# InkTime.net
KiCad netlist of a schematic drawn in EAGLE
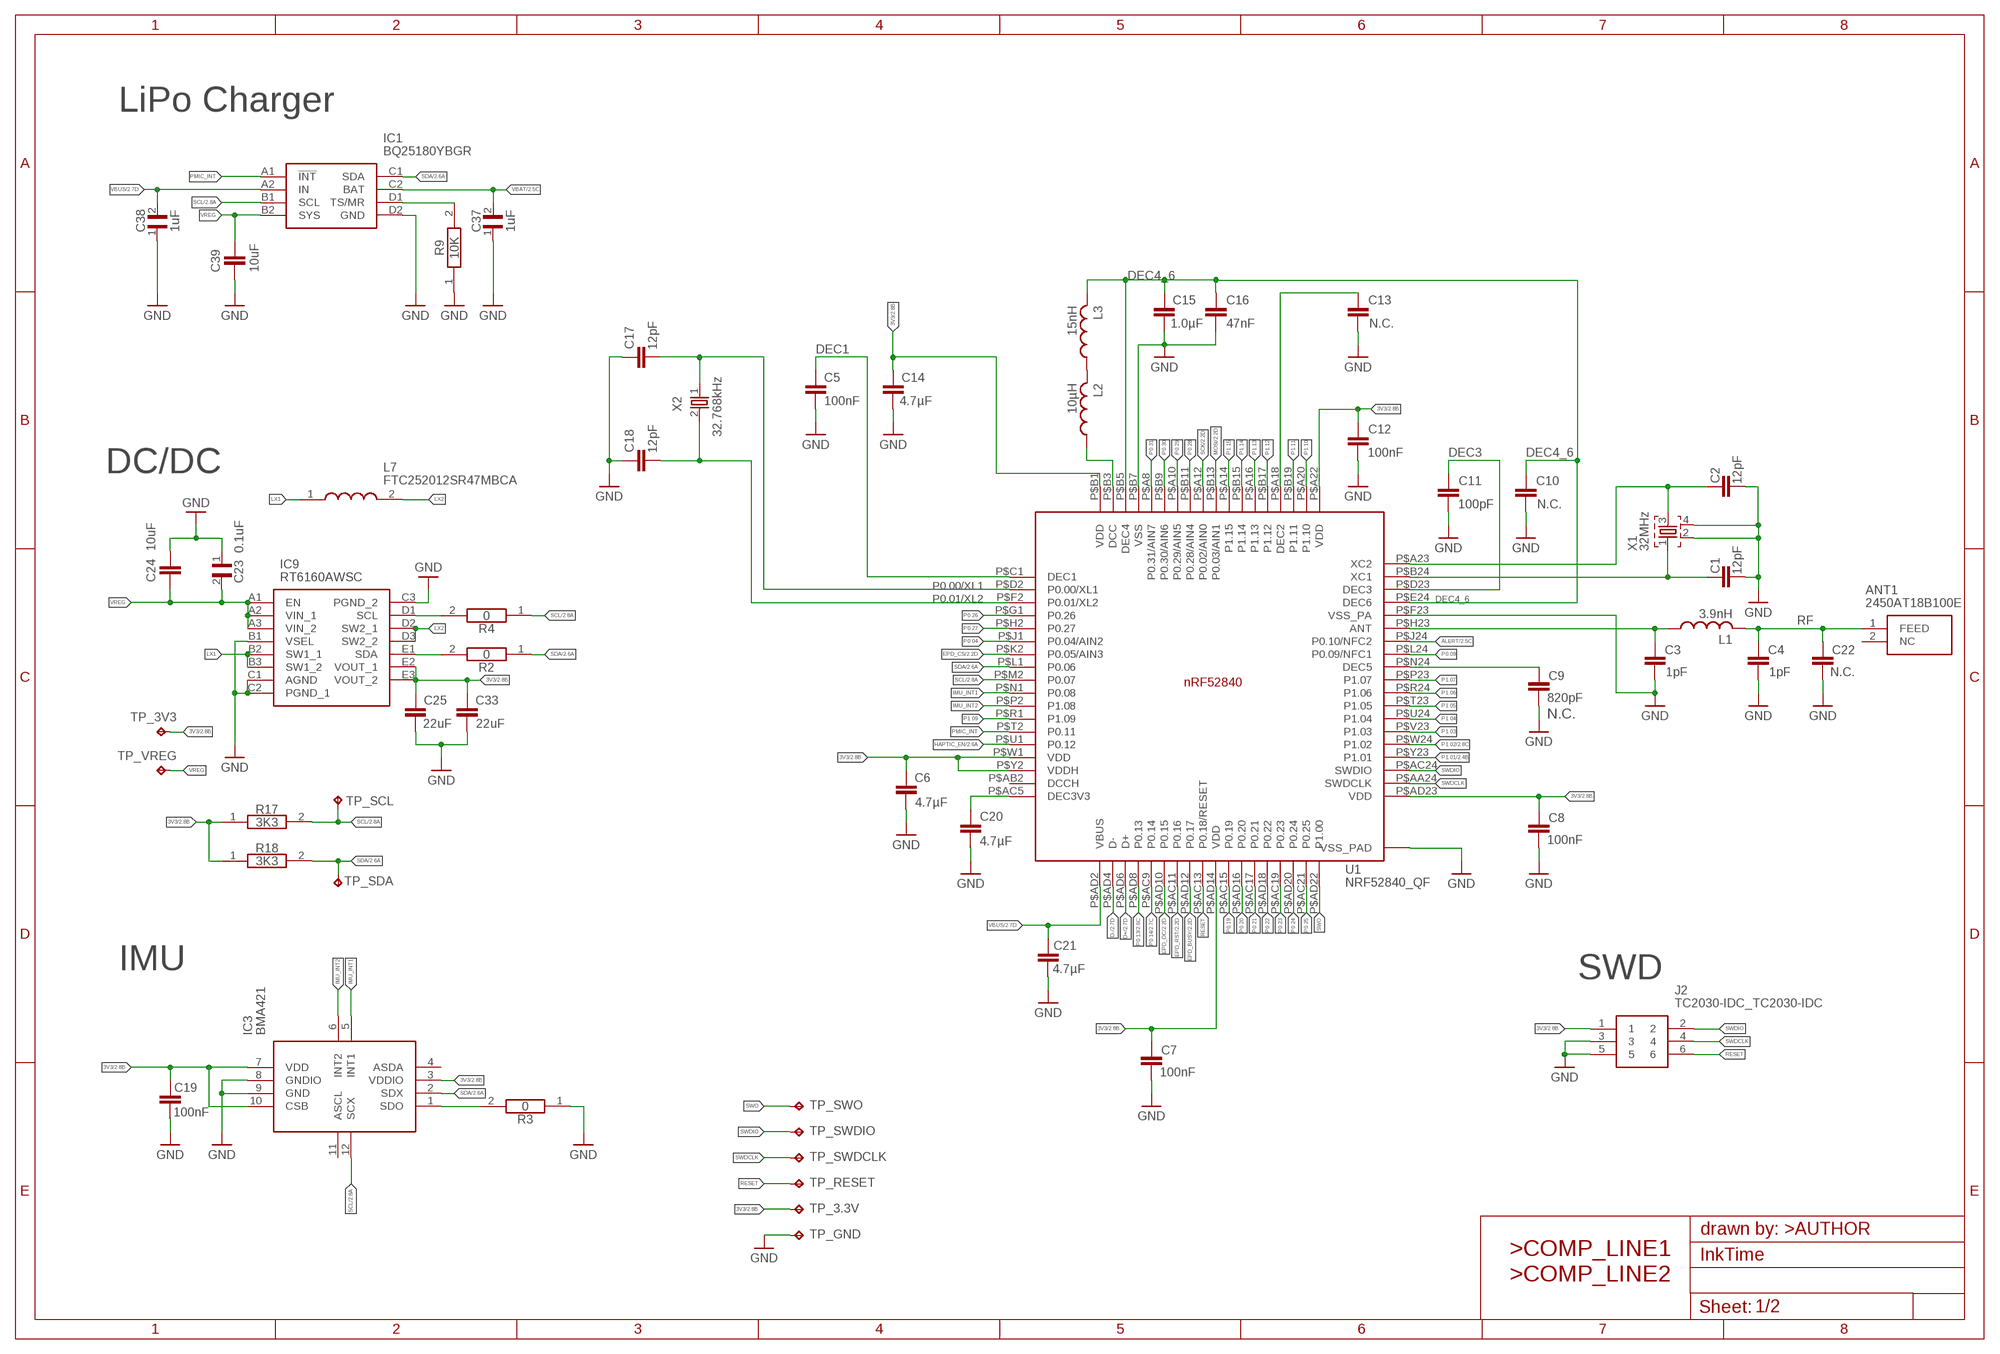
[diagram p0: schematic, sheet 1]
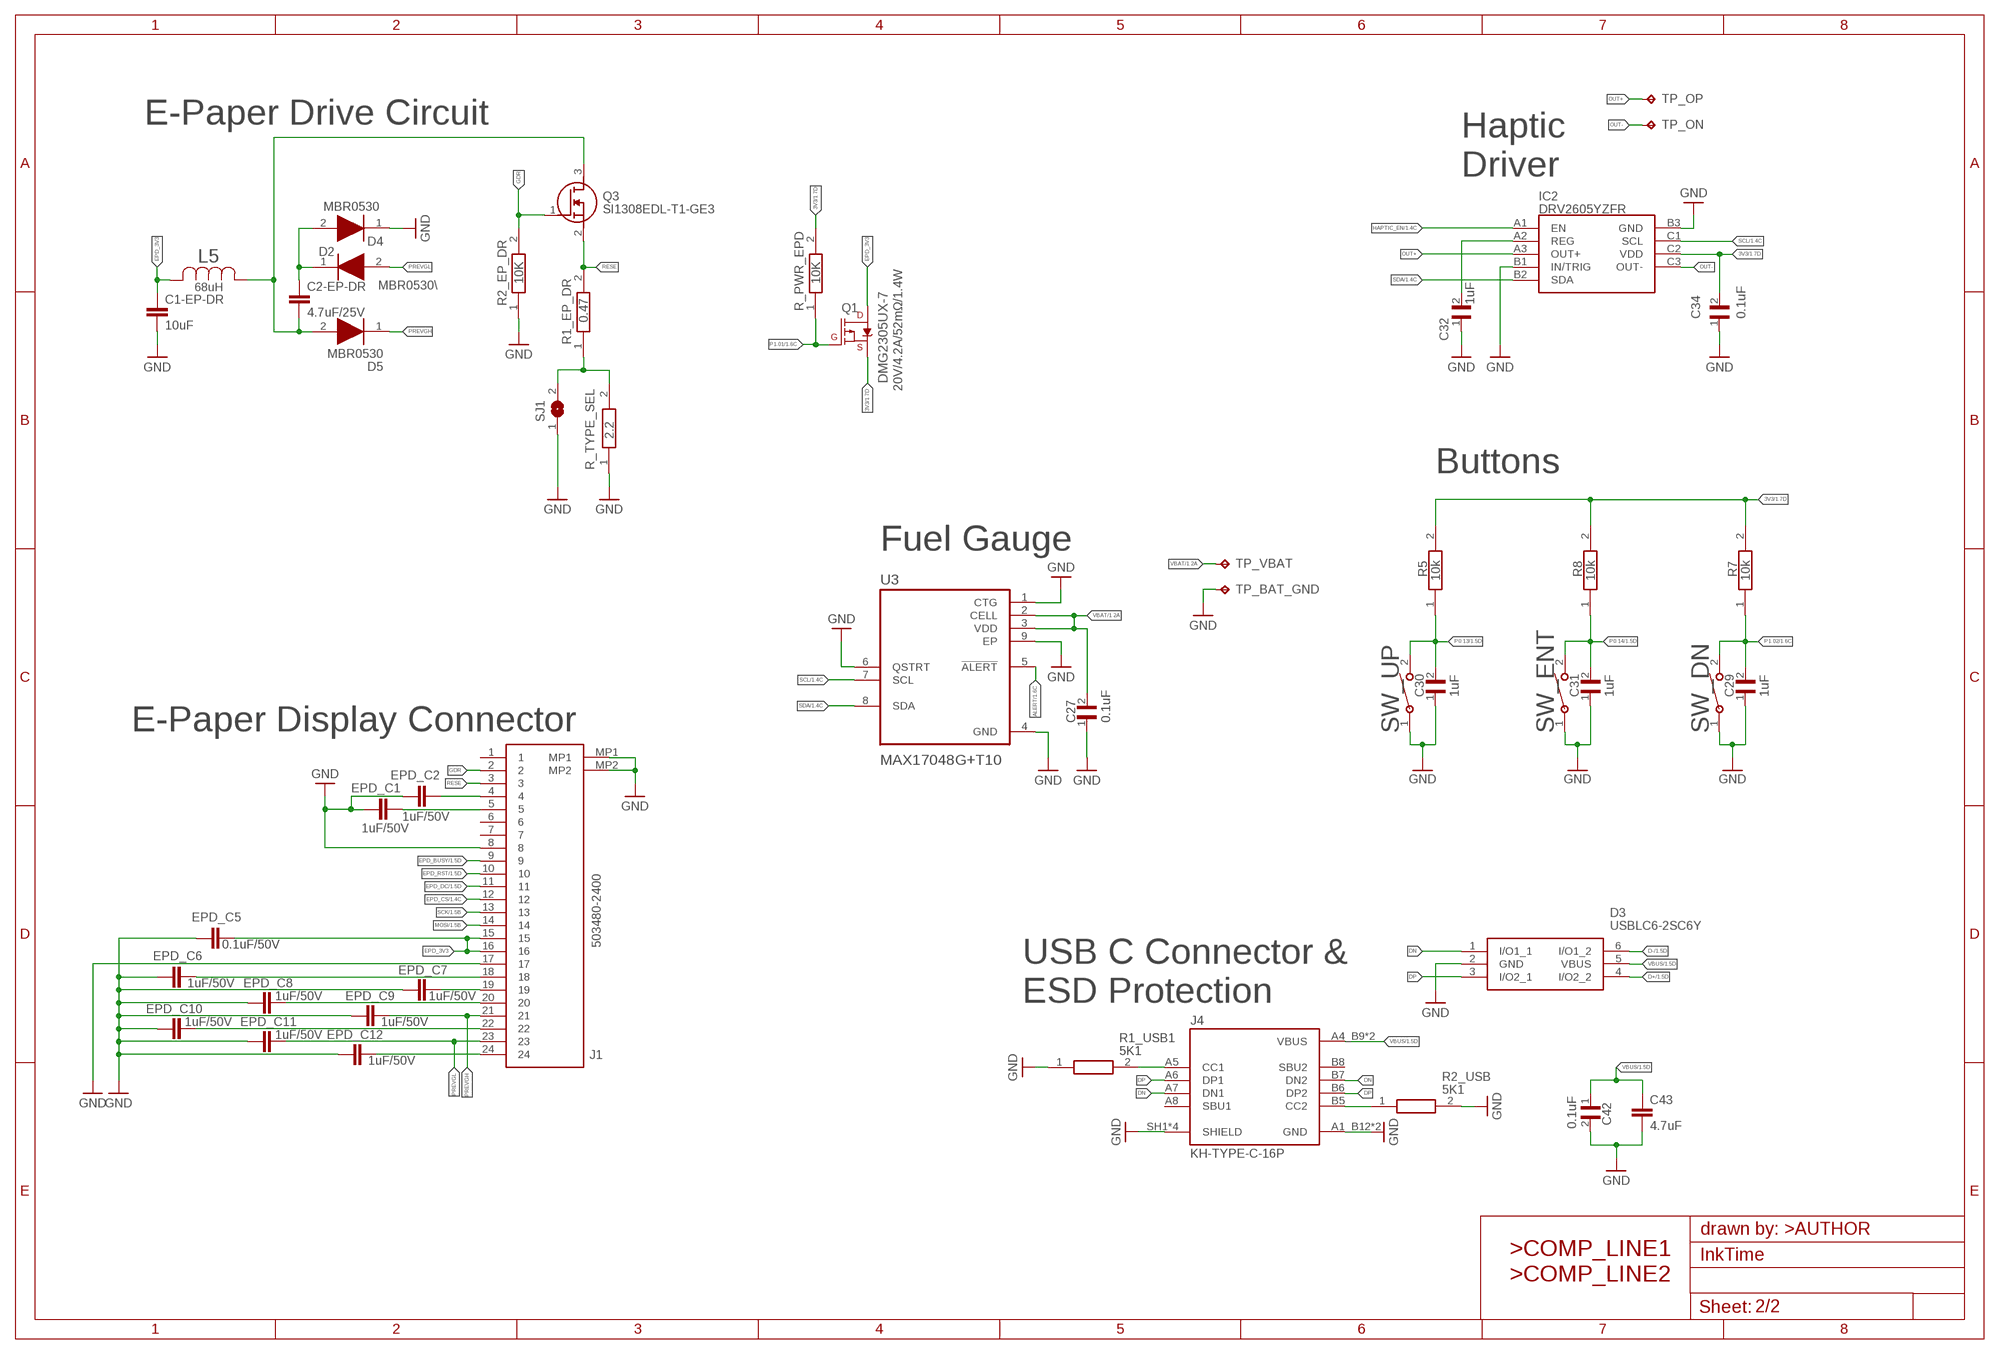
[diagram p1: schematic, sheet 2]

(export (version "E")
  (design (tool "Eeschema 10.0.6"))
  (components
    (comp (ref "ANT1")
      (value "2450AT18B100E")
      (footprint "eagle-import:2450AT18B100E_ANTC3216X140N")
      (fields (field (name "MOUSER_PART_NUMBER") "609-2450AT18B100E"))
      (libsource (lib "eagle-import") (part "2450AT18B100E_2450AT18B100E"))
    )
    (comp (ref "C1")
      (value "12pF")
      (footprint "eagle-import:NORDIC_NRF_3_RESC0201_L")
      (libsource (lib "eagle-import") (part "NORDIC_NRF_3_CAPACITOR_0201_L"))
    )
    (comp (ref "C2")
      (value "12pF")
      (footprint "eagle-import:NORDIC_NRF_3_RESC0201_L")
      (libsource (lib "eagle-import") (part "NORDIC_NRF_3_CAPACITOR_0201_L"))
    )
    (comp (ref "C3")
      (value "1pF")
      (footprint "eagle-import:NORDIC_NRF_3_RESC0201_L")
      (libsource (lib "eagle-import") (part "NORDIC_NRF_3_CAPACITOR_0201_L"))
    )
    (comp (ref "C4")
      (value "1pF")
      (footprint "eagle-import:NORDIC_NRF_3_RESC0201_L")
      (libsource (lib "eagle-import") (part "NORDIC_NRF_3_CAPACITOR_0201_L"))
    )
    (comp (ref "C5")
      (value "100nF")
      (footprint "eagle-import:NORDIC_NRF_3_RESC0201_L")
      (libsource (lib "eagle-import") (part "NORDIC_NRF_3_CAPACITOR_0201_L"))
    )
    (comp (ref "C6")
      (value "4.7µF")
      (footprint "eagle-import:NORDIC_NRF_3_RESC0402_L")
      (libsource (lib "eagle-import") (part "NORDIC_NRF_3_CAPACITOR_0402_L"))
    )
    (comp (ref "C7")
      (value "100nF")
      (footprint "eagle-import:NORDIC_NRF_3_RESC0201_L")
      (libsource (lib "eagle-import") (part "NORDIC_NRF_3_CAPACITOR_0201_L"))
    )
    (comp (ref "C8")
      (value "100nF")
      (footprint "eagle-import:NORDIC_NRF_3_RESC0201_L")
      (libsource (lib "eagle-import") (part "NORDIC_NRF_3_CAPACITOR_0201_L"))
    )
    (comp (ref "C9")
      (value "820pF")
      (footprint "eagle-import:NORDIC_NRF_3_RESC0201_L")
      (libsource (lib "eagle-import") (part "NORDIC_NRF_3_CAPACITOR_0201_L"))
    )
    (comp (ref "C10")
      (value "N.C.")
      (footprint "eagle-import:NORDIC_NRF_3_RESC0201_L")
      (libsource (lib "eagle-import") (part "NORDIC_NRF_3_CAPACITOR_0201_L"))
    )
    (comp (ref "C11")
      (value "100pF")
      (footprint "eagle-import:NORDIC_NRF_3_RESC0201_L")
      (libsource (lib "eagle-import") (part "NORDIC_NRF_3_CAPACITOR_0201_L"))
    )
    (comp (ref "C12")
      (value "100nF")
      (footprint "eagle-import:NORDIC_NRF_3_RESC0201_L")
      (libsource (lib "eagle-import") (part "NORDIC_NRF_3_CAPACITOR_0201_L"))
    )
    (comp (ref "C13")
      (value "N.C.")
      (footprint "eagle-import:NORDIC_NRF_3_RESC0201_L")
      (libsource (lib "eagle-import") (part "NORDIC_NRF_3_CAPACITOR_0201_L"))
    )
    (comp (ref "C14")
      (value "4.7µF")
      (footprint "eagle-import:NORDIC_NRF_3_RESC0402_L")
      (libsource (lib "eagle-import") (part "NORDIC_NRF_3_CAPACITOR_0402_L"))
    )
    (comp (ref "C15")
      (value "1.0µF")
      (footprint "eagle-import:NORDIC_NRF_3_RESC0402_L")
      (libsource (lib "eagle-import") (part "NORDIC_NRF_3_CAPACITOR_0402_L"))
    )
    (comp (ref "C16")
      (value "47nF")
      (footprint "eagle-import:NORDIC_NRF_3_RESC0201_L")
      (libsource (lib "eagle-import") (part "NORDIC_NRF_3_CAPACITOR_0201_L"))
    )
    (comp (ref "C17")
      (value "12pF")
      (footprint "eagle-import:NORDIC_NRF_3_RESC0201_L")
      (libsource (lib "eagle-import") (part "NORDIC_NRF_3_CAPACITOR_0201_L"))
    )
    (comp (ref "C18")
      (value "12pF")
      (footprint "eagle-import:NORDIC_NRF_3_RESC0201_L")
      (libsource (lib "eagle-import") (part "NORDIC_NRF_3_CAPACITOR_0201_L"))
    )
    (comp (ref "C19")
      (value "100nF")
      (footprint "eagle-import:NORDIC_NRF_3_RESC0201_L")
      (libsource (lib "eagle-import") (part "NORDIC_NRF_3_CAPACITOR_0201_L"))
    )
    (comp (ref "C20")
      (value "4.7µF")
      (footprint "eagle-import:NORDIC_NRF_3_RESC0402_L")
      (libsource (lib "eagle-import") (part "NORDIC_NRF_3_CAPACITOR_0402_L"))
    )
    (comp (ref "C21")
      (value "4.7µF")
      (footprint "eagle-import:NORDIC_NRF_3_RESC0402_L")
      (libsource (lib "eagle-import") (part "NORDIC_NRF_3_CAPACITOR_0402_L"))
    )
    (comp (ref "C22")
      (value "N.C.")
      (footprint "eagle-import:NORDIC_NRF_3_RESC0201_L")
      (libsource (lib "eagle-import") (part "NORDIC_NRF_3_CAPACITOR_0201_L"))
    )
    (comp (ref "C23")
      (value "0.1uF")
      (footprint "eagle-import:GRM011R60J152KE01L_1_0201")
      (libsource (lib "eagle-import") (part "GRM011R60J152KE01L_1_GRM011R60J152KE01L"))
    )
    (comp (ref "C24")
      (value "10uF")
      (footprint "eagle-import:NORDIC_NRF_3_RESC0402_L")
      (libsource (lib "eagle-import") (part "NORDIC_NRF_3_CAPACITOR_0402_L"))
    )
    (comp (ref "C25")
      (value "22uF")
      (footprint "eagle-import:NORDIC_NRF_3_RESC0402_L")
      (libsource (lib "eagle-import") (part "NORDIC_NRF_3_CAPACITOR_0402_L"))
    )
    (comp (ref "C33")
      (value "22uF")
      (footprint "eagle-import:NORDIC_NRF_3_RESC0402_L")
      (libsource (lib "eagle-import") (part "NORDIC_NRF_3_CAPACITOR_0402_L"))
    )
    (comp (ref "C37")
      (value "1uF")
      (footprint "eagle-import:GRM011R60J152KE01L_1_0201")
      (libsource (lib "eagle-import") (part "GRM011R60J152KE01L_1_GRM011R60J152KE01L"))
    )
    (comp (ref "C38")
      (value "1uF")
      (footprint "eagle-import:GRM011R60J152KE01L_1_0201")
      (libsource (lib "eagle-import") (part "GRM011R60J152KE01L_1_GRM011R60J152KE01L"))
    )
    (comp (ref "C39")
      (value "10uF")
      (footprint "eagle-import:NORDIC_NRF_3_RESC0402_L")
      (libsource (lib "eagle-import") (part "NORDIC_NRF_3_CAPACITOR_0402_L"))
    )
    (comp (ref "IC1")
      (value "BQ25180YBGR")
      (footprint "eagle-import:BQ25180YBGR_BGA8C40P2X4_100X155X50")
      (fields (field (name "MOUSER_PART_NUMBER") "595-BQ25180YBGR"))
      (libsource (lib "eagle-import") (part "BQ25180YBGR_BQ25180YBGR"))
    )
    (comp (ref "IC3")
      (value "BMA421")
      (footprint "eagle-import:BMA423_BMA423")
      (fields (field (name "ARROW_PART_NUMBER") "BMA423") (field (name "MOUSER_PART_NUMBER") "262-BMA423"))
      (libsource (lib "eagle-import") (part "BMA423_BMA423"))
    )
    (comp (ref "IC9")
      (value "RT6160AWSC")
      (footprint "eagle-import:RT6160AWSC_BGA15C40P3X5_140X230X60")
      (fields (field (name "MOUSER_PART_NUMBER") "835-RT6160AWSC"))
      (libsource (lib "eagle-import") (part "RT6160AWSC_RT6160AWSC"))
    )
    (comp (ref "J2")
      (value "TC2030-IDC_TC2030-IDC")
      (footprint "eagle-import:TC2030-IDC_TC2030IDC")
      (fields (field (name "MANUFACTURER_PART_NUMBER") "TC2030-IDC"))
      (libsource (lib "eagle-import") (part "TC2030-IDC_TC2030-IDC"))
    )
    (comp (ref "L1")
      (value "3.9nH")
      (footprint "eagle-import:NORDIC_NRF_2_RESC0402_L")
      (libsource (lib "eagle-import") (part "NORDIC_NRF_2_INDUCTOR_0402_L"))
    )
    (comp (ref "L2")
      (value "10µH")
      (footprint "eagle-import:NORDIC_NRF_2_RESC0402_L")
      (libsource (lib "eagle-import") (part "NORDIC_NRF_2_INDUCTOR_0402_L"))
    )
    (comp (ref "L3")
      (value "15nH")
      (footprint "eagle-import:NORDIC_NRF_2_RESC0402_L")
      (libsource (lib "eagle-import") (part "NORDIC_NRF_2_INDUCTOR_0402_L"))
    )
    (comp (ref "L7")
      (value "FTC252012SR47MBCA")
      (footprint "eagle-import:MLP2016SR47MT0S1_INDC2016X100N")
      (libsource (lib "eagle-import") (part "MLP2016SR47MT0S1_FTC252012SR47MBCA"))
    )
    (comp (ref "R2")
      (value "0")
      (footprint "eagle-import:CPF0201D7K68C1_0201")
      (libsource (lib "eagle-import") (part "CPF0201D7K68C1_CPF0201D7K68C1"))
    )
    (comp (ref "R3")
      (value "0")
      (footprint "eagle-import:CPF0201D7K68C1_0201")
      (libsource (lib "eagle-import") (part "CPF0201D7K68C1_CPF0201D7K68C1"))
    )
    (comp (ref "R4")
      (value "0")
      (footprint "eagle-import:CPF0201D7K68C1_0201")
      (libsource (lib "eagle-import") (part "CPF0201D7K68C1_CPF0201D7K68C1"))
    )
    (comp (ref "R9")
      (value "10K")
      (footprint "eagle-import:CPF0201D7K68C1_0201")
      (libsource (lib "eagle-import") (part "CPF0201D7K68C1_CPF0201D7K68C1"))
    )
    (comp (ref "R17")
      (value "3K3")
      (footprint "eagle-import:CPF0201D7K68C1_0201")
      (libsource (lib "eagle-import") (part "CPF0201D7K68C1_CPF0201D7K68C1"))
    )
    (comp (ref "R18")
      (value "3K3")
      (footprint "eagle-import:CPF0201D7K68C1_0201")
      (libsource (lib "eagle-import") (part "CPF0201D7K68C1_CPF0201D7K68C1"))
    )
    (comp (ref "TP_3.3V")
      (value "HECTOR_WATCH_1_TPTP20R")
      (footprint "eagle-import:HECTOR_WATCH_1_TP20R")
      (libsource (lib "eagle-import") (part "HECTOR_WATCH_1_TPTP20R"))
    )
    (comp (ref "TP_3V3")
      (value "HECTOR_WATCH_1_TPTP20R")
      (footprint "eagle-import:HECTOR_WATCH_1_TP20R")
      (libsource (lib "eagle-import") (part "HECTOR_WATCH_1_TPTP20R"))
    )
    (comp (ref "TP_GND")
      (value "HECTOR_WATCH_1_TPTP20R")
      (footprint "eagle-import:HECTOR_WATCH_1_TP20R")
      (libsource (lib "eagle-import") (part "HECTOR_WATCH_1_TPTP20R"))
    )
    (comp (ref "TP_RESET")
      (value "HECTOR_WATCH_1_TPTP20R")
      (footprint "eagle-import:HECTOR_WATCH_1_TP20R")
      (libsource (lib "eagle-import") (part "HECTOR_WATCH_1_TPTP20R"))
    )
    (comp (ref "TP_SCL")
      (value "HECTOR_WATCH_1_TPTP20R")
      (footprint "eagle-import:HECTOR_WATCH_1_TP20R")
      (libsource (lib "eagle-import") (part "HECTOR_WATCH_1_TPTP20R"))
    )
    (comp (ref "TP_SDA")
      (value "HECTOR_WATCH_1_TPTP20R")
      (footprint "eagle-import:HECTOR_WATCH_1_TP20R")
      (libsource (lib "eagle-import") (part "HECTOR_WATCH_1_TPTP20R"))
    )
    (comp (ref "TP_SWDCLK")
      (value "HECTOR_WATCH_1_TPTP20R")
      (footprint "eagle-import:HECTOR_WATCH_1_TP20R")
      (libsource (lib "eagle-import") (part "HECTOR_WATCH_1_TPTP20R"))
    )
    (comp (ref "TP_SWDIO")
      (value "HECTOR_WATCH_1_TPTP20R")
      (footprint "eagle-import:HECTOR_WATCH_1_TP20R")
      (libsource (lib "eagle-import") (part "HECTOR_WATCH_1_TPTP20R"))
    )
    (comp (ref "TP_SWO")
      (value "HECTOR_WATCH_1_TPTP20R")
      (footprint "eagle-import:HECTOR_WATCH_1_TP20R")
      (libsource (lib "eagle-import") (part "HECTOR_WATCH_1_TPTP20R"))
    )
    (comp (ref "TP_VREG")
      (value "HECTOR_WATCH_1_TPTP20R")
      (footprint "eagle-import:HECTOR_WATCH_1_TP20R")
      (libsource (lib "eagle-import") (part "HECTOR_WATCH_1_TPTP20R"))
    )
    (comp (ref "U1")
      (value "NRF52840_QF")
      (footprint "eagle-import:NORDIC_NRF_4_AQFN50P700X700X85_HS-74N")
      (libsource (lib "eagle-import") (part "NORDIC_NRF_4_NRF52840_QF"))
    )
    (comp (ref "X1")
      (value "32MHz")
      (footprint "eagle-import:NORDIC_NRF_BT-XTAL_2016_N")
      (libsource (lib "eagle-import") (part "NORDIC_NRF_XTAL_32MHZ"))
    )
    (comp (ref "X2")
      (value "32.768kHz")
      (footprint "eagle-import:NORDIC_NRF_1_XTAL_3215_N")
      (libsource (lib "eagle-import") (part "NORDIC_NRF_1_XTAL_32KHZ"))
    )
    (comp (ref "C1-EP-DR")
      (value "10uF")
      (footprint "eagle-import:NORDIC_NRF_3_RESC0402_L")
      (libsource (lib "eagle-import") (part "NORDIC_NRF_3_CAPACITOR_0402_L"))
    )
    (comp (ref "C2-EP-DR")
      (value "4.7uF/25V")
      (footprint "eagle-import:NORDIC_NRF_3_RESC0402_L")
      (libsource (lib "eagle-import") (part "NORDIC_NRF_3_CAPACITOR_0402_L"))
    )
    (comp (ref "C27")
      (value "0.1uF")
      (footprint "eagle-import:GRM011R60J152KE01L_1_0201")
      (libsource (lib "eagle-import") (part "GRM011R60J152KE01L_1_GRM011R60J152KE01L"))
    )
    (comp (ref "C29")
      (value "1uF")
      (footprint "eagle-import:GRM011R60J152KE01L_1_0201")
      (libsource (lib "eagle-import") (part "GRM011R60J152KE01L_1_GRM011R60J152KE01L"))
    )
    (comp (ref "C30")
      (value "1uF")
      (footprint "eagle-import:GRM011R60J152KE01L_1_0201")
      (libsource (lib "eagle-import") (part "GRM011R60J152KE01L_1_GRM011R60J152KE01L"))
    )
    (comp (ref "C31")
      (value "1uF")
      (footprint "eagle-import:GRM011R60J152KE01L_1_0201")
      (libsource (lib "eagle-import") (part "GRM011R60J152KE01L_1_GRM011R60J152KE01L"))
    )
    (comp (ref "C32")
      (value "1uF")
      (footprint "eagle-import:GRM011R60J152KE01L_1_0201")
      (libsource (lib "eagle-import") (part "GRM011R60J152KE01L_1_GRM011R60J152KE01L"))
    )
    (comp (ref "C34")
      (value "0.1uF")
      (footprint "eagle-import:GRM011R60J152KE01L_1_0201")
      (libsource (lib "eagle-import") (part "GRM011R60J152KE01L_1_GRM011R60J152KE01L"))
    )
    (comp (ref "C42")
      (value "0.1uF")
      (footprint "eagle-import:GRM011R60J152KE01L_1_0201")
      (libsource (lib "eagle-import") (part "GRM011R60J152KE01L_1_GRM011R60J152KE01L"))
    )
    (comp (ref "C43")
      (value "4.7uF")
      (footprint "eagle-import:NORDIC_NRF_3_RESC0402_L")
      (libsource (lib "eagle-import") (part "NORDIC_NRF_3_CAPACITOR_0402_L"))
    )
    (comp (ref "D2")
      (value "MBR0530\\")
      (footprint "eagle-import:ESP32_C6_LIBRARY_5_SOD3716X135N")
      (fields (field (name "MF") "ON Semiconductor") (field (name "MP") "MBR0530"))
      (libsource (lib "eagle-import") (part "ESP32_C6_LIBRARY_5_MBR0530"))
    )
    (comp (ref "D3")
      (value "USBLC6-2SC6Y")
      (footprint "eagle-import:ESP32_C6_LIBRARY_3_SOT95P280X145-6N")
      (fields (field (name "MF") "STMicroelectronics"))
      (libsource (lib "eagle-import") (part "ESP32_C6_LIBRARY_3_USBLC6-2SC6Y"))
    )
    (comp (ref "D4")
      (value "MBR0530")
      (footprint "eagle-import:ESP32_C6_LIBRARY_5_SOD3716X135N")
      (fields (field (name "MF") "ON Semiconductor"))
      (libsource (lib "eagle-import") (part "ESP32_C6_LIBRARY_5_MBR0530"))
    )
    (comp (ref "D5")
      (value "MBR0530")
      (footprint "eagle-import:ESP32_C6_LIBRARY_5_SOD3716X135N")
      (fields (field (name "MF") "ON Semiconductor"))
      (libsource (lib "eagle-import") (part "ESP32_C6_LIBRARY_5_MBR0530"))
    )
    (comp (ref "EPD_C1")
      (value "1uF/50V")
      (footprint "eagle-import:NORDIC_NRF_3_RESC0402_L")
      (libsource (lib "eagle-import") (part "NORDIC_NRF_3_CAPACITOR_0402_L"))
    )
    (comp (ref "EPD_C2")
      (value "1uF/50V")
      (footprint "eagle-import:NORDIC_NRF_3_RESC0402_L")
      (libsource (lib "eagle-import") (part "NORDIC_NRF_3_CAPACITOR_0402_L"))
    )
    (comp (ref "EPD_C5")
      (value "0.1uF/50V")
      (footprint "eagle-import:NORDIC_NRF_3_RESC0201_L")
      (libsource (lib "eagle-import") (part "NORDIC_NRF_3_CAPACITOR_0201_L"))
    )
    (comp (ref "EPD_C6")
      (value "1uF/50V")
      (footprint "eagle-import:NORDIC_NRF_3_RESC0402_L")
      (libsource (lib "eagle-import") (part "NORDIC_NRF_3_CAPACITOR_0402_L"))
    )
    (comp (ref "EPD_C7")
      (value "1uF/50V")
      (footprint "eagle-import:NORDIC_NRF_3_RESC0402_L")
      (libsource (lib "eagle-import") (part "NORDIC_NRF_3_CAPACITOR_0402_L"))
    )
    (comp (ref "EPD_C8")
      (value "1uF/50V")
      (footprint "eagle-import:NORDIC_NRF_3_RESC0402_L")
      (libsource (lib "eagle-import") (part "NORDIC_NRF_3_CAPACITOR_0402_L"))
    )
    (comp (ref "EPD_C9")
      (value "1uF/50V")
      (footprint "eagle-import:NORDIC_NRF_3_RESC0402_L")
      (libsource (lib "eagle-import") (part "NORDIC_NRF_3_CAPACITOR_0402_L"))
    )
    (comp (ref "EPD_C10")
      (value "1uF/50V")
      (footprint "eagle-import:NORDIC_NRF_3_RESC0402_L")
      (libsource (lib "eagle-import") (part "NORDIC_NRF_3_CAPACITOR_0402_L"))
    )
    (comp (ref "EPD_C11")
      (value "1uF/50V")
      (footprint "eagle-import:NORDIC_NRF_3_RESC0402_L")
      (libsource (lib "eagle-import") (part "NORDIC_NRF_3_CAPACITOR_0402_L"))
    )
    (comp (ref "EPD_C12")
      (value "1uF/50V")
      (footprint "eagle-import:NORDIC_NRF_3_RESC0402_L")
      (libsource (lib "eagle-import") (part "NORDIC_NRF_3_CAPACITOR_0402_L"))
    )
    (comp (ref "IC2")
      (value "DRV2605YZFR")
      (footprint "eagle-import:DRV2605YZFR_BGA9C50P3X3_144X144X62")
      (libsource (lib "eagle-import") (part "DRV2605YZFR_DRV2605YZFR"))
    )
    (comp (ref "J1")
      (value "503480-2400")
      (footprint "eagle-import:503480-2400_5034802400")
      (fields (field (name "MOUSER_PART_NUMBER") "538-503480-2400"))
      (libsource (lib "eagle-import") (part "503480-2400_503480-2400"))
    )
    (comp (ref "J4")
      (value "KH-TYPE-C-16P")
      (footprint "eagle-import:KH-TYPE-C-16P_KINGHELM_KH-TYPE-C-16P")
      (fields (field (name "MF") "kinghelm"))
      (libsource (lib "eagle-import") (part "KH-TYPE-C-16P_KH-TYPE-C-16P"))
    )
    (comp (ref "L5")
      (value "68uH")
      (footprint "eagle-import:ESP32_C6_LIBRARY_2_IND_4828-WE-TPC_WRE")
      (fields
        (field (name "MANUFACTURER_PART_NUMBER") "744043680")
        (field (name "COPYRIGHT") "Copyright (C) 2024 Ultra Librarian. All rights reserved.")
      )
      (libsource (lib "eagle-import") (part "ESP32_C6_LIBRARY_2_744043680IND_4828-WE-TPC_WRE"))
    )
    (comp (ref "Q1")
      (value "20V/4.2A/52mΩ/1.4W")
      (footprint "eagle-import:ESP32_C6_LIBRARY_4_ESP32_C6_LIBRARY_4_ESP32_C6_LIBRARY_4_ESP32_C6_LIBRARY_4_ESP32_WROVER_SPARKFUN-DISCRETESEMI_SOT23-3")
      (libsource (lib "eagle-import") (part "ESP32_C6_LIBRARY_4_ESP32_WROVER_SPARKFUN-DISCRETESEMI_MOSFET_PCH-DMG2305UX-7"))
    )
    (comp (ref "Q3")
      (value "SI1308EDL-T1-GE3")
      (footprint "eagle-import:ESP32_C6_LIBRARY_6_SOT65P210X110-3N")
      (fields (field (name "MF") "Vishay Siliconix"))
      (libsource (lib "eagle-import") (part "ESP32_C6_LIBRARY_6_SI1308EDL-T1-GE3"))
    )
    (comp (ref "R1_EP_DR")
      (value "0.47")
      (footprint "eagle-import:CPF0201D7K68C1_0201")
      (libsource (lib "eagle-import") (part "CPF0201D7K68C1_CPF0201D7K68C1"))
    )
    (comp (ref "R1_USB1")
      (value "5K1")
      (footprint "eagle-import:CPF0201D7K68C1_0201")
      (libsource (lib "eagle-import") (part "CPF0201D7K68C1_CPF0201D7K68C1"))
    )
    (comp (ref "R2_EP_DR")
      (value "10K")
      (footprint "eagle-import:CPF0201D7K68C1_0201")
      (libsource (lib "eagle-import") (part "CPF0201D7K68C1_CPF0201D7K68C1"))
    )
    (comp (ref "R2_USB")
      (value "5K1")
      (footprint "eagle-import:CPF0201D7K68C1_0201")
      (libsource (lib "eagle-import") (part "CPF0201D7K68C1_CPF0201D7K68C1"))
    )
    (comp (ref "R5")
      (value "10k")
      (footprint "eagle-import:CPF0201D7K68C1_0201")
      (libsource (lib "eagle-import") (part "CPF0201D7K68C1_CPF0201D7K68C1"))
    )
    (comp (ref "R7")
      (value "10k")
      (footprint "eagle-import:CPF0201D7K68C1_0201")
      (libsource (lib "eagle-import") (part "CPF0201D7K68C1_CPF0201D7K68C1"))
    )
    (comp (ref "R8")
      (value "10k")
      (footprint "eagle-import:CPF0201D7K68C1_0201")
      (libsource (lib "eagle-import") (part "CPF0201D7K68C1_CPF0201D7K68C1"))
    )
    (comp (ref "R_PWR_EPD")
      (value "10K")
      (footprint "eagle-import:CPF0201D7K68C1_0201")
      (libsource (lib "eagle-import") (part "CPF0201D7K68C1_CPF0201D7K68C1"))
    )
    (comp (ref "R_TYPE_SEL")
      (value "2.2")
      (footprint "eagle-import:CPF0201D7K68C1_0201")
      (libsource (lib "eagle-import") (part "CPF0201D7K68C1_CPF0201D7K68C1"))
    )
    (comp (ref "SJ1")
      (value "ESP32_C6_LIBRARY_7_JUMPER_SJ")
      (footprint "eagle-import:ESP32_C6_LIBRARY_7_JUMPER_SJ")
      (libsource (lib "eagle-import") (part "ESP32_C6_LIBRARY_7_JUMPER_SJ"))
    )
    (comp (ref "SW_DN")
      (value "2025-10-22_07-23-44_LIBRARY_EVP-AKE31ASW_EVP-AKE31A_PAN")
      (footprint "eagle-import:2025-10-22_07-23-44_LIBRARY_SW_EVP-AKE31A_PAN")
      (fields
        (field (name "MANUFACTURER_PART_NUMBER") "EVP-AKE31A")
        (field (name "COPYRIGHT") "Copyright (C) 2025 Ultra Librarian. All rights reserved.")
      )
      (libsource (lib "eagle-import") (part "2025-10-22_07-23-44_LIBRARY_EVP-AKE31ASW_EVP-AKE31A_PAN"))
    )
    (comp (ref "SW_ENT")
      (value "2025-10-22_07-23-44_LIBRARY_EVP-AKE31ASW_EVP-AKE31A_PAN")
      (footprint "eagle-import:2025-10-22_07-23-44_LIBRARY_SW_EVP-AKE31A_PAN")
      (fields
        (field (name "MANUFACTURER_PART_NUMBER") "EVP-AKE31A")
        (field (name "COPYRIGHT") "Copyright (C) 2025 Ultra Librarian. All rights reserved.")
      )
      (libsource (lib "eagle-import") (part "2025-10-22_07-23-44_LIBRARY_EVP-AKE31ASW_EVP-AKE31A_PAN"))
    )
    (comp (ref "SW_UP")
      (value "2025-10-22_07-23-44_LIBRARY_EVP-AKE31ASW_EVP-AKE31A_PAN")
      (footprint "eagle-import:2025-10-22_07-23-44_LIBRARY_SW_EVP-AKE31A_PAN")
      (fields
        (field (name "MANUFACTURER_PART_NUMBER") "EVP-AKE31A")
        (field (name "COPYRIGHT") "Copyright (C) 2025 Ultra Librarian. All rights reserved.")
      )
      (libsource (lib "eagle-import") (part "2025-10-22_07-23-44_LIBRARY_EVP-AKE31ASW_EVP-AKE31A_PAN"))
    )
    (comp (ref "TP_BAT_GND")
      (value "HECTOR_WATCH_1_TPTP20R")
      (footprint "eagle-import:HECTOR_WATCH_1_TP20R")
      (libsource (lib "eagle-import") (part "HECTOR_WATCH_1_TPTP20R"))
    )
    (comp (ref "TP_ON")
      (value "HECTOR_WATCH_1_TPTP20R")
      (footprint "eagle-import:HECTOR_WATCH_1_TP20R")
      (libsource (lib "eagle-import") (part "HECTOR_WATCH_1_TPTP20R"))
    )
    (comp (ref "TP_OP")
      (value "HECTOR_WATCH_1_TPTP20R")
      (footprint "eagle-import:HECTOR_WATCH_1_TP20R")
      (libsource (lib "eagle-import") (part "HECTOR_WATCH_1_TPTP20R"))
    )
    (comp (ref "TP_VBAT")
      (value "HECTOR_WATCH_1_TPTP20R")
      (footprint "eagle-import:HECTOR_WATCH_1_TP20R")
      (libsource (lib "eagle-import") (part "HECTOR_WATCH_1_TPTP20R"))
    )
    (comp (ref "U3")
      (value "MAX17048G+T10")
      (footprint "eagle-import:ESP32_C6_LIBRARY_SON50P200X200X80-9N")
      (fields (field (name "MF") "Analog Devices"))
      (libsource (lib "eagle-import") (part "ESP32_C6_LIBRARY_MAX17048G+T10"))
    )
  )
  (nets
    (net (code "1") (name "3V3") (class "Default")
      (node (ref "C12") (pin "1") (pinfunction "1_1") (pintype "passive"))
      (node (ref "C14") (pin "1") (pinfunction "1_1") (pintype "passive"))
      (node (ref "C19") (pin "1") (pinfunction "1_1") (pintype "passive"))
      (node (ref "C25") (pin "1") (pinfunction "1_1") (pintype "passive"))
      (node (ref "C33") (pin "1") (pinfunction "1_1") (pintype "passive"))
      (node (ref "C34") (pin "2") (pinfunction "2_2") (pintype "passive"))
      (node (ref "C6") (pin "1") (pinfunction "1_1") (pintype "passive"))
      (node (ref "C7") (pin "1") (pinfunction "1_1") (pintype "passive"))
      (node (ref "C8") (pin "1") (pinfunction "1_1") (pintype "passive"))
      (node (ref "IC2") (pin "C2") (pinfunction "VDD_C2") (pintype "bidirectional"))
      (node (ref "IC3") (pin "10") (pinfunction "CSB_10") (pintype "bidirectional"))
      (node (ref "IC3") (pin "3") (pinfunction "VDDIO_3") (pintype "bidirectional"))
      (node (ref "IC3") (pin "7") (pinfunction "VDD_7") (pintype "bidirectional"))
      (node (ref "IC9") (pin "E2") (pinfunction "VOUT_1_E2") (pintype "bidirectional"))
      (node (ref "IC9") (pin "E3") (pinfunction "VOUT_2_E3") (pintype "bidirectional"))
      (node (ref "J2") (pin "1") (pinfunction "1_1") (pintype "bidirectional"))
      (node (ref "Q1") (pin "2") (pinfunction "S_2") (pintype "bidirectional"))
      (node (ref "R17") (pin "1") (pinfunction "1_1") (pintype "bidirectional"))
      (node (ref "R18") (pin "1") (pinfunction "1_1") (pintype "bidirectional"))
      (node (ref "R5") (pin "2") (pinfunction "2_2") (pintype "bidirectional"))
      (node (ref "R7") (pin "2") (pinfunction "2_2") (pintype "bidirectional"))
      (node (ref "R8") (pin "2") (pinfunction "2_2") (pintype "bidirectional"))
      (node (ref "R_PWR_EPD") (pin "2") (pinfunction "2_2") (pintype "bidirectional"))
      (node (ref "TP_3.3V") (pin "TP") (pinfunction "TP_TP") (pintype "input"))
      (node (ref "TP_3V3") (pin "TP") (pinfunction "TP_TP") (pintype "input"))
      (node (ref "U1") (pin "P$A22") (pinfunction "VDD_P$A22") (pintype "power_in"))
      (node (ref "U1") (pin "P$AD14") (pinfunction "VDD_P$AD14") (pintype "power_in"))
      (node (ref "U1") (pin "P$AD23") (pinfunction "VDD_P$AD23") (pintype "power_in"))
      (node (ref "U1") (pin "P$B1") (pinfunction "VDD_P$B1") (pintype "power_in"))
      (node (ref "U1") (pin "P$W1") (pinfunction "VDD_P$W1") (pintype "power_in"))
      (node (ref "U1") (pin "P$Y2") (pinfunction "VDDH_P$Y2") (pintype "power_in"))
    )
    (net (code "2") (name "ALERT") (class "Default")
      (node (ref "U1") (pin "P$J24") (pinfunction "P0.10/NFC2_P$J24") (pintype "bidirectional"))
      (node (ref "U3") (pin "5") (pinfunction "~{ALERT}_5") (pintype "output"))
    )
    (net (code "3") (name "D+") (class "Default")
      (node (ref "D3") (pin "4") (pinfunction "I/O2_2_4") (pintype "bidirectional"))
      (node (ref "U1") (pin "P$AD6") (pinfunction "D+_P$AD6") (pintype "bidirectional"))
    )
    (net (code "4") (name "D-") (class "Default")
      (node (ref "D3") (pin "6") (pinfunction "I/O1_2_6") (pintype "bidirectional"))
      (node (ref "U1") (pin "P$AD4") (pinfunction "D-_P$AD4") (pintype "bidirectional"))
    )
    (net (code "5") (name "DN") (class "Default")
      (node (ref "D3") (pin "1") (pinfunction "I/O1_1_1") (pintype "bidirectional"))
      (node (ref "J4") (pin "A7") (pinfunction "DN1_A7") (pintype "bidirectional"))
      (node (ref "J4") (pin "B7") (pinfunction "DN2_B7") (pintype "bidirectional"))
    )
    (net (code "6") (name "DP") (class "Default")
      (node (ref "D3") (pin "3") (pinfunction "I/O2_1_3") (pintype "bidirectional"))
      (node (ref "J4") (pin "A6") (pinfunction "DP1_A6") (pintype "bidirectional"))
      (node (ref "J4") (pin "B6") (pinfunction "DP2_B6") (pintype "bidirectional"))
    )
    (net (code "7") (name "EPD_3V3") (class "Default")
      (node (ref "C1-EP-DR") (pin "2") (pinfunction "2_2") (pintype "passive"))
      (node (ref "EPD_C5") (pin "2") (pinfunction "2_2") (pintype "passive"))
      (node (ref "J1") (pin "15") (pinfunction "15_15") (pintype "bidirectional"))
      (node (ref "J1") (pin "16") (pinfunction "16_16") (pintype "bidirectional"))
      (node (ref "L5") (pin "2") (pinfunction "2_2") (pintype "passive"))
      (node (ref "Q1") (pin "3") (pinfunction "D_3") (pintype "bidirectional"))
    )
    (net (code "8") (name "EPD_BUSY") (class "Default")
      (node (ref "J1") (pin "9") (pinfunction "9_9") (pintype "bidirectional"))
      (node (ref "U1") (pin "P$AD12") (pinfunction "P0.17_P$AD12") (pintype "bidirectional"))
    )
    (net (code "9") (name "EPD_CS") (class "Default")
      (node (ref "J1") (pin "12") (pinfunction "12_12") (pintype "bidirectional"))
      (node (ref "U1") (pin "P$K2") (pinfunction "P0.05/AIN3_P$K2") (pintype "bidirectional"))
    )
    (net (code "10") (name "EPD_DC") (class "Default")
      (node (ref "J1") (pin "11") (pinfunction "11_11") (pintype "bidirectional"))
      (node (ref "U1") (pin "P$AD10") (pinfunction "P0.15_P$AD10") (pintype "bidirectional"))
    )
    (net (code "11") (name "EPD_RST") (class "Default")
      (node (ref "J1") (pin "10") (pinfunction "10_10") (pintype "bidirectional"))
      (node (ref "U1") (pin "P$AC11") (pinfunction "P0.16_P$AC11") (pintype "bidirectional"))
    )
    (net (code "12") (name "GDR") (class "Default")
      (node (ref "J1") (pin "2") (pinfunction "2_2") (pintype "bidirectional"))
      (node (ref "Q3") (pin "1") (pinfunction "G_1") (pintype "bidirectional"))
      (node (ref "R2_EP_DR") (pin "2") (pinfunction "2_2") (pintype "bidirectional"))
    )
    (net (code "13") (name "GND") (class "Default")
      (node (ref "C1") (pin "2") (pinfunction "2_2") (pintype "passive"))
      (node (ref "C1-EP-DR") (pin "1") (pinfunction "1_1") (pintype "passive"))
      (node (ref "C10") (pin "2") (pinfunction "2_2") (pintype "passive"))
      (node (ref "C11") (pin "2") (pinfunction "2_2") (pintype "passive"))
      (node (ref "C12") (pin "2") (pinfunction "2_2") (pintype "passive"))
      (node (ref "C13") (pin "2") (pinfunction "2_2") (pintype "passive"))
      (node (ref "C14") (pin "2") (pinfunction "2_2") (pintype "passive"))
      (node (ref "C15") (pin "2") (pinfunction "2_2") (pintype "passive"))
      (node (ref "C16") (pin "2") (pinfunction "2_2") (pintype "passive"))
      (node (ref "C17") (pin "1") (pinfunction "1_1") (pintype "passive"))
      (node (ref "C18") (pin "1") (pinfunction "1_1") (pintype "passive"))
      (node (ref "C19") (pin "2") (pinfunction "2_2") (pintype "passive"))
      (node (ref "C2") (pin "2") (pinfunction "2_2") (pintype "passive"))
      (node (ref "C20") (pin "2") (pinfunction "2_2") (pintype "passive"))
      (node (ref "C21") (pin "2") (pinfunction "2_2") (pintype "passive"))
      (node (ref "C22") (pin "2") (pinfunction "2_2") (pintype "passive"))
      (node (ref "C23") (pin "1") (pinfunction "1_1") (pintype "passive"))
      (node (ref "C24") (pin "1") (pinfunction "1_1") (pintype "passive"))
      (node (ref "C25") (pin "2") (pinfunction "2_2") (pintype "passive"))
      (node (ref "C27") (pin "1") (pinfunction "1_1") (pintype "passive"))
      (node (ref "C29") (pin "1") (pinfunction "1_1") (pintype "passive"))
      (node (ref "C3") (pin "2") (pinfunction "2_2") (pintype "passive"))
      (node (ref "C30") (pin "1") (pinfunction "1_1") (pintype "passive"))
      (node (ref "C31") (pin "1") (pinfunction "1_1") (pintype "passive"))
      (node (ref "C32") (pin "1") (pinfunction "1_1") (pintype "passive"))
      (node (ref "C33") (pin "2") (pinfunction "2_2") (pintype "passive"))
      (node (ref "C34") (pin "1") (pinfunction "1_1") (pintype "passive"))
      (node (ref "C37") (pin "1") (pinfunction "1_1") (pintype "passive"))
      (node (ref "C38") (pin "1") (pinfunction "1_1") (pintype "passive"))
      (node (ref "C39") (pin "2") (pinfunction "2_2") (pintype "passive"))
      (node (ref "C4") (pin "2") (pinfunction "2_2") (pintype "passive"))
      (node (ref "C42") (pin "2") (pinfunction "2_2") (pintype "passive"))
      (node (ref "C43") (pin "2") (pinfunction "2_2") (pintype "passive"))
      (node (ref "C5") (pin "2") (pinfunction "2_2") (pintype "passive"))
      (node (ref "C6") (pin "2") (pinfunction "2_2") (pintype "passive"))
      (node (ref "C7") (pin "2") (pinfunction "2_2") (pintype "passive"))
      (node (ref "C8") (pin "2") (pinfunction "2_2") (pintype "passive"))
      (node (ref "C9") (pin "2") (pinfunction "2_2") (pintype "passive"))
      (node (ref "D3") (pin "2") (pinfunction "GND_2") (pintype "bidirectional"))
      (node (ref "D4") (pin "1") (pinfunction "K_1") (pintype "bidirectional"))
      (node (ref "EPD_C1") (pin "1") (pinfunction "1_1") (pintype "passive"))
      (node (ref "EPD_C10") (pin "1") (pinfunction "1_1") (pintype "passive"))
      (node (ref "EPD_C11") (pin "1") (pinfunction "1_1") (pintype "passive"))
      (node (ref "EPD_C12") (pin "1") (pinfunction "1_1") (pintype "passive"))
      (node (ref "EPD_C2") (pin "1") (pinfunction "1_1") (pintype "passive"))
      (node (ref "EPD_C5") (pin "1") (pinfunction "1_1") (pintype "passive"))
      (node (ref "EPD_C6") (pin "1") (pinfunction "1_1") (pintype "passive"))
      (node (ref "EPD_C7") (pin "1") (pinfunction "1_1") (pintype "passive"))
      (node (ref "EPD_C8") (pin "1") (pinfunction "1_1") (pintype "passive"))
      (node (ref "EPD_C9") (pin "1") (pinfunction "1_1") (pintype "passive"))
      (node (ref "IC1") (pin "D2") (pinfunction "GND_D2") (pintype "bidirectional"))
      (node (ref "IC2") (pin "B1") (pinfunction "IN/TRIG_B1") (pintype "bidirectional"))
      (node (ref "IC2") (pin "B3") (pinfunction "GND_B3") (pintype "bidirectional"))
      (node (ref "IC3") (pin "8") (pinfunction "GNDIO_8") (pintype "bidirectional"))
      (node (ref "IC3") (pin "9") (pinfunction "GND_9") (pintype "bidirectional"))
      (node (ref "IC9") (pin "B1") (pinfunction "VSEL_B1") (pintype "bidirectional"))
      (node (ref "IC9") (pin "C1") (pinfunction "AGND_C1") (pintype "bidirectional"))
      (node (ref "IC9") (pin "C2") (pinfunction "PGND_1_C2") (pintype "bidirectional"))
      (node (ref "IC9") (pin "C3") (pinfunction "PGND_2_C3") (pintype "bidirectional"))
      (node (ref "J1") (pin "17") (pinfunction "17_17") (pintype "bidirectional"))
      (node (ref "J1") (pin "8") (pinfunction "8_8") (pintype "bidirectional"))
      (node (ref "J1") (pin "MP1") (pinfunction "MP1_MP1") (pintype "bidirectional"))
      (node (ref "J1") (pin "MP2") (pinfunction "MP2_MP2") (pintype "bidirectional"))
      (node (ref "J2") (pin "3") (pinfunction "3_3") (pintype "bidirectional"))
      (node (ref "J2") (pin "5") (pinfunction "5_5") (pintype "bidirectional"))
      (node (ref "J4") (pin "A12_B1") (pinfunction "GND_A12_B1") (pintype "power_in"))
      (node (ref "J4") (pin "A1_B12") (pinfunction "GND_A1_B12") (pintype "power_in"))
      (node (ref "J4") (pin "SH1") (pinfunction "SHIELD_SH1") (pintype "passive"))
      (node (ref "J4") (pin "SH2") (pinfunction "SHIELD_SH2") (pintype "passive"))
      (node (ref "J4") (pin "SH3") (pinfunction "SHIELD_SH3") (pintype "passive"))
      (node (ref "J4") (pin "SH4") (pinfunction "SHIELD_SH4") (pintype "passive"))
      (node (ref "R1_USB1") (pin "1") (pinfunction "1_1") (pintype "bidirectional"))
      (node (ref "R2_EP_DR") (pin "1") (pinfunction "1_1") (pintype "bidirectional"))
      (node (ref "R2_USB") (pin "2") (pinfunction "2_2") (pintype "bidirectional"))
      (node (ref "R3") (pin "1") (pinfunction "1_1") (pintype "bidirectional"))
      (node (ref "R9") (pin "1") (pinfunction "1_1") (pintype "bidirectional"))
      (node (ref "R_TYPE_SEL") (pin "1") (pinfunction "1_1") (pintype "bidirectional"))
      (node (ref "SJ1") (pin "1") (pinfunction "1_1") (pintype "passive"))
      (node (ref "SW_DN") (pin "1") (pinfunction "1_1") (pintype "passive"))
      (node (ref "SW_ENT") (pin "1") (pinfunction "1_1") (pintype "passive"))
      (node (ref "SW_UP") (pin "1") (pinfunction "1_1") (pintype "passive"))
      (node (ref "TP_BAT_GND") (pin "TP") (pinfunction "TP_TP") (pintype "input"))
      (node (ref "TP_GND") (pin "TP") (pinfunction "TP_TP") (pintype "input"))
      (node (ref "U1") (pin "P$74") (pinfunction "VSS_PAD_P$74") (pintype "bidirectional"))
      (node (ref "U1") (pin "P$75") (pinfunction "VSS_PAD_P$75") (pintype "bidirectional"))
      (node (ref "U1") (pin "P$76") (pinfunction "VSS_PAD_P$76") (pintype "bidirectional"))
      (node (ref "U1") (pin "P$77") (pinfunction "VSS_PAD_P$77") (pintype "bidirectional"))
      (node (ref "U1") (pin "P$78") (pinfunction "VSS_PAD_P$78") (pintype "bidirectional"))
      (node (ref "U1") (pin "P$79") (pinfunction "VSS_PAD_P$79") (pintype "bidirectional"))
      (node (ref "U1") (pin "P$80") (pinfunction "VSS_PAD_P$80") (pintype "bidirectional"))
      (node (ref "U1") (pin "P$81") (pinfunction "VSS_PAD_P$81") (pintype "bidirectional"))
      (node (ref "U1") (pin "P$82") (pinfunction "VSS_PAD_P$82") (pintype "bidirectional"))
      (node (ref "U1") (pin "P$83") (pinfunction "VSS_PAD_P$83") (pintype "bidirectional"))
      (node (ref "U1") (pin "P$84") (pinfunction "VSS_PAD_P$84") (pintype "bidirectional"))
      (node (ref "U1") (pin "P$85") (pinfunction "VSS_PAD_P$85") (pintype "bidirectional"))
      (node (ref "U1") (pin "P$86") (pinfunction "VSS_PAD_P$86") (pintype "bidirectional"))
      (node (ref "U1") (pin "P$87") (pinfunction "VSS_PAD_P$87") (pintype "bidirectional"))
      (node (ref "U1") (pin "P$88") (pinfunction "VSS_PAD_P$88") (pintype "bidirectional"))
      (node (ref "U1") (pin "P$89") (pinfunction "VSS_PAD_P$89") (pintype "bidirectional"))
      (node (ref "U1") (pin "P$90") (pinfunction "VSS_PAD_P$90") (pintype "bidirectional"))
      (node (ref "U1") (pin "P$B7") (pinfunction "VSS_P$B7") (pintype "power_in"))
      (node (ref "U1") (pin "P$F23") (pinfunction "VSS_PA_P$F23") (pintype "bidirectional"))
      (node (ref "U3") (pin "1") (pinfunction "CTG_1") (pintype "power_in"))
      (node (ref "U3") (pin "4") (pinfunction "GND_4") (pintype "power_in"))
      (node (ref "U3") (pin "6") (pinfunction "QSTRT_6") (pintype "input"))
      (node (ref "U3") (pin "9") (pinfunction "EP_9") (pintype "power_in"))
      (node (ref "X1") (pin "2") (pinfunction "2_2") (pintype "passive"))
      (node (ref "X1") (pin "4") (pinfunction "4_4") (pintype "passive"))
    )
    (net (code "14") (name "HAPTIC_EN") (class "Default")
      (node (ref "IC2") (pin "A1") (pinfunction "EN_A1") (pintype "bidirectional"))
      (node (ref "U1") (pin "P$U1") (pinfunction "P0.12_P$U1") (pintype "bidirectional"))
    )
    (net (code "15") (name "IMU_INT1") (class "Default")
      (node (ref "IC3") (pin "5") (pinfunction "INT1_5") (pintype "bidirectional"))
      (node (ref "U1") (pin "P$N1") (pinfunction "P0.08_P$N1") (pintype "bidirectional"))
    )
    (net (code "16") (name "IMU_INT2") (class "Default")
      (node (ref "IC3") (pin "6") (pinfunction "INT2_6") (pintype "bidirectional"))
      (node (ref "U1") (pin "P$P2") (pinfunction "P1.08_P$P2") (pintype "bidirectional"))
    )
    (net (code "17") (name "LX1") (class "Default")
      (node (ref "IC9") (pin "B2") (pinfunction "SW1_1_B2") (pintype "bidirectional"))
      (node (ref "IC9") (pin "B3") (pinfunction "SW1_2_B3") (pintype "bidirectional"))
      (node (ref "L7") (pin "1") (pinfunction "1_1") (pintype "bidirectional"))
    )
    (net (code "18") (name "LX2") (class "Default")
      (node (ref "IC9") (pin "D2") (pinfunction "SW2_1_D2") (pintype "bidirectional"))
      (node (ref "IC9") (pin "D3") (pinfunction "SW2_2_D3") (pintype "bidirectional"))
      (node (ref "L7") (pin "2") (pinfunction "2_2") (pintype "bidirectional"))
    )
    (net (code "19") (name "MOSI") (class "Default")
      (node (ref "J1") (pin "14") (pinfunction "14_14") (pintype "bidirectional"))
      (node (ref "U1") (pin "P$B13") (pinfunction "P0.03/AIN1_P$B13") (pintype "bidirectional"))
    )
    (net (code "20") (name "Net-(ANT1-FEED)") (class "Default")
      (node (ref "ANT1") (pin "1") (pinfunction "FEED_1") (pintype "input"))
      (node (ref "C22") (pin "1") (pinfunction "1_1") (pintype "passive"))
      (node (ref "C4") (pin "1") (pinfunction "1_1") (pintype "passive"))
      (node (ref "L1") (pin "2") (pinfunction "2_2") (pintype "passive"))
    )
    (net (code "21") (name "Net-(D2-K)") (class "Default")
      (node (ref "C2-EP-DR") (pin "2") (pinfunction "2_2") (pintype "passive"))
      (node (ref "D2") (pin "1") (pinfunction "K_1") (pintype "bidirectional"))
      (node (ref "D4") (pin "2") (pinfunction "A_2") (pintype "bidirectional"))
    )
    (net (code "22") (name "Net-(D5-A)") (class "Default")
      (node (ref "C2-EP-DR") (pin "1") (pinfunction "1_1") (pintype "passive"))
      (node (ref "D5") (pin "2") (pinfunction "A_2") (pintype "bidirectional"))
      (node (ref "L5") (pin "1") (pinfunction "1_1") (pintype "passive"))
      (node (ref "Q3") (pin "3") (pinfunction "D_3") (pintype "bidirectional"))
    )
    (net (code "23") (name "Net-(EPD_C1-Pad2)") (class "Default")
      (node (ref "EPD_C1") (pin "2") (pinfunction "2_2") (pintype "passive"))
      (node (ref "J1") (pin "5") (pinfunction "5_5") (pintype "bidirectional"))
    )
    (net (code "24") (name "Net-(EPD_C2-Pad2)") (class "Default")
      (node (ref "EPD_C2") (pin "2") (pinfunction "2_2") (pintype "passive"))
      (node (ref "J1") (pin "4") (pinfunction "4_4") (pintype "bidirectional"))
    )
    (net (code "25") (name "Net-(EPD_C6-Pad2)") (class "Default")
      (node (ref "EPD_C6") (pin "2") (pinfunction "2_2") (pintype "passive"))
      (node (ref "J1") (pin "18") (pinfunction "18_18") (pintype "bidirectional"))
    )
    (net (code "26") (name "Net-(EPD_C7-Pad2)") (class "Default")
      (node (ref "EPD_C7") (pin "2") (pinfunction "2_2") (pintype "passive"))
      (node (ref "J1") (pin "19") (pinfunction "19_19") (pintype "bidirectional"))
    )
    (net (code "27") (name "Net-(EPD_C8-Pad2)") (class "Default")
      (node (ref "EPD_C8") (pin "2") (pinfunction "2_2") (pintype "passive"))
      (node (ref "J1") (pin "20") (pinfunction "20_20") (pintype "bidirectional"))
    )
    (net (code "28") (name "Net-(EPD_C10-Pad2)") (class "Default")
      (node (ref "EPD_C10") (pin "2") (pinfunction "2_2") (pintype "passive"))
      (node (ref "J1") (pin "22") (pinfunction "22_22") (pintype "bidirectional"))
    )
    (net (code "29") (name "Net-(EPD_C12-Pad2)") (class "Default")
      (node (ref "EPD_C12") (pin "2") (pinfunction "2_2") (pintype "passive"))
      (node (ref "J1") (pin "24") (pinfunction "24_24") (pintype "bidirectional"))
    )
    (net (code "30") (name "Net-(IC1-TS{slash}MR)") (class "Default")
      (node (ref "IC1") (pin "D1") (pinfunction "TS/MR_D1") (pintype "bidirectional"))
      (node (ref "R9") (pin "2") (pinfunction "2_2") (pintype "bidirectional"))
    )
    (net (code "31") (name "Net-(IC2-REG)") (class "Default")
      (node (ref "C32") (pin "2") (pinfunction "2_2") (pintype "passive"))
      (node (ref "IC2") (pin "A2") (pinfunction "REG_A2") (pintype "bidirectional"))
    )
    (net (code "32") (name "Net-(IC3-SDO)") (class "Default")
      (node (ref "IC3") (pin "1") (pinfunction "SDO_1") (pintype "bidirectional"))
      (node (ref "R3") (pin "2") (pinfunction "2_2") (pintype "bidirectional"))
    )
    (net (code "33") (name "Net-(IC9-SCL)") (class "Default")
      (node (ref "IC9") (pin "D1") (pinfunction "SCL_D1") (pintype "bidirectional"))
      (node (ref "R4") (pin "2") (pinfunction "2_2") (pintype "bidirectional"))
    )
    (net (code "34") (name "Net-(IC9-SDA)") (class "Default")
      (node (ref "IC9") (pin "E1") (pinfunction "SDA_E1") (pintype "bidirectional"))
      (node (ref "R2") (pin "2") (pinfunction "2_2") (pintype "bidirectional"))
    )
    (net (code "35") (name "Net-(J4-CC1)") (class "Default")
      (node (ref "J4") (pin "A5") (pinfunction "CC1_A5") (pintype "bidirectional"))
      (node (ref "R1_USB1") (pin "2") (pinfunction "2_2") (pintype "bidirectional"))
    )
    (net (code "36") (name "Net-(J4-CC2)") (class "Default")
      (node (ref "J4") (pin "B5") (pinfunction "CC2_B5") (pintype "bidirectional"))
      (node (ref "R2_USB") (pin "1") (pinfunction "1_1") (pintype "bidirectional"))
    )
    (net (code "37") (name "Net-(L2-Pad2)") (class "Default")
      (node (ref "L2") (pin "2") (pinfunction "2_2") (pintype "passive"))
      (node (ref "L3") (pin "1") (pinfunction "1_1") (pintype "passive"))
    )
    (net (code "38") (name "Net-(R1_EP_DR-Pad1)") (class "Default")
      (node (ref "R1_EP_DR") (pin "1") (pinfunction "1_1") (pintype "bidirectional"))
      (node (ref "R_TYPE_SEL") (pin "2") (pinfunction "2_2") (pintype "bidirectional"))
      (node (ref "SJ1") (pin "2") (pinfunction "2_2") (pintype "passive"))
    )
    (net (code "39") (name "Net-(U1-ANT)") (class "Default")
      (node (ref "C3") (pin "1") (pinfunction "1_1") (pintype "passive"))
      (node (ref "L1") (pin "1") (pinfunction "1_1") (pintype "passive"))
      (node (ref "U1") (pin "P$H23") (pinfunction "ANT_P$H23") (pintype "bidirectional"))
    )
    (net (code "40") (name "Net-(U1-DCC)") (class "Default")
      (node (ref "L2") (pin "1") (pinfunction "1_1") (pintype "passive"))
      (node (ref "U1") (pin "P$B3") (pinfunction "DCC_P$B3") (pintype "output"))
    )
    (net (code "41") (name "Net-(U1-DEC1)") (class "Default")
      (node (ref "C5") (pin "1") (pinfunction "1_1") (pintype "passive"))
      (node (ref "U1") (pin "P$C1") (pinfunction "DEC1_P$C1") (pintype "power_in"))
    )
    (net (code "42") (name "Net-(U1-DEC2)") (class "Default")
      (node (ref "C13") (pin "1") (pinfunction "1_1") (pintype "passive"))
      (node (ref "U1") (pin "P$A18") (pinfunction "DEC2_P$A18") (pintype "bidirectional"))
    )
    (net (code "43") (name "Net-(U1-DEC3)") (class "Default")
      (node (ref "C11") (pin "1") (pinfunction "1_1") (pintype "passive"))
      (node (ref "U1") (pin "P$D23") (pinfunction "DEC3_P$D23") (pintype "bidirectional"))
    )
    (net (code "44") (name "Net-(U1-DEC3V3)") (class "Default")
      (node (ref "C20") (pin "1") (pinfunction "1_1") (pintype "passive"))
      (node (ref "U1") (pin "P$AC5") (pinfunction "DEC3V3_P$AC5") (pintype "bidirectional"))
    )
    (net (code "45") (name "Net-(U1-DEC4)") (class "Default")
      (node (ref "C10") (pin "1") (pinfunction "1_1") (pintype "passive"))
      (node (ref "C15") (pin "1") (pinfunction "1_1") (pintype "passive"))
      (node (ref "C16") (pin "1") (pinfunction "1_1") (pintype "passive"))
      (node (ref "L3") (pin "2") (pinfunction "2_2") (pintype "passive"))
      (node (ref "U1") (pin "P$B5") (pinfunction "DEC4_P$B5") (pintype "power_in"))
      (node (ref "U1") (pin "P$E24") (pinfunction "DEC6_P$E24") (pintype "bidirectional"))
    )
    (net (code "46") (name "Net-(U1-DEC5)") (class "Default")
      (node (ref "C9") (pin "1") (pinfunction "1_1") (pintype "passive"))
      (node (ref "U1") (pin "P$N24") (pinfunction "DEC5_P$N24") (pintype "bidirectional"))
    )
    (net (code "47") (name "Net-(U1-P0.00{slash}XL1)") (class "Default")
      (node (ref "C17") (pin "2") (pinfunction "2_2") (pintype "passive"))
      (node (ref "U1") (pin "P$D2") (pinfunction "P0.00/XL1_P$D2") (pintype "bidirectional"))
      (node (ref "X2") (pin "1") (pinfunction "1_1") (pintype "passive"))
    )
    (net (code "48") (name "Net-(U1-P0.01{slash}XL2)") (class "Default")
      (node (ref "C18") (pin "2") (pinfunction "2_2") (pintype "passive"))
      (node (ref "U1") (pin "P$F2") (pinfunction "P0.01/XL2_P$F2") (pintype "bidirectional"))
      (node (ref "X2") (pin "2") (pinfunction "2_2") (pintype "passive"))
    )
    (net (code "49") (name "Net-(U1-XC1)") (class "Default")
      (node (ref "C1") (pin "1") (pinfunction "1_1") (pintype "passive"))
      (node (ref "U1") (pin "P$B24") (pinfunction "XC1_P$B24") (pintype "input"))
      (node (ref "X1") (pin "1") (pinfunction "1_1") (pintype "passive"))
    )
    (net (code "50") (name "Net-(U1-XC2)") (class "Default")
      (node (ref "C2") (pin "1") (pinfunction "1_1") (pintype "passive"))
      (node (ref "U1") (pin "P$A23") (pinfunction "XC2_P$A23") (pintype "output"))
      (node (ref "X1") (pin "3") (pinfunction "3_3") (pintype "passive"))
    )
    (net (code "51") (name "OUT+") (class "Default")
      (node (ref "IC2") (pin "A3") (pinfunction "OUT+_A3") (pintype "bidirectional"))
      (node (ref "TP_OP") (pin "TP") (pinfunction "TP_TP") (pintype "input"))
    )
    (net (code "52") (name "OUT-") (class "Default")
      (node (ref "IC2") (pin "C3") (pinfunction "OUT-_C3") (pintype "bidirectional"))
      (node (ref "TP_ON") (pin "TP") (pinfunction "TP_TP") (pintype "input"))
    )
    (net (code "53") (name "P0.04") (class "Default")
      (node (ref "U1") (pin "P$J1") (pinfunction "P0.04/AIN2_P$J1") (pintype "bidirectional"))
    )
    (net (code "54") (name "P0.09") (class "Default")
      (node (ref "U1") (pin "P$L24") (pinfunction "P0.09/NFC1_P$L24") (pintype "bidirectional"))
    )
    (net (code "55") (name "P0.13") (class "Default")
      (node (ref "C30") (pin "2") (pinfunction "2_2") (pintype "passive"))
      (node (ref "R5") (pin "1") (pinfunction "1_1") (pintype "bidirectional"))
      (node (ref "SW_UP") (pin "2") (pinfunction "2_2") (pintype "passive"))
      (node (ref "U1") (pin "P$AD8") (pinfunction "P0.13_P$AD8") (pintype "bidirectional"))
    )
    (net (code "56") (name "P0.14") (class "Default")
      (node (ref "C31") (pin "2") (pinfunction "2_2") (pintype "passive"))
      (node (ref "R8") (pin "1") (pinfunction "1_1") (pintype "bidirectional"))
      (node (ref "SW_ENT") (pin "2") (pinfunction "2_2") (pintype "passive"))
      (node (ref "U1") (pin "P$AC9") (pinfunction "P0.14_P$AC9") (pintype "bidirectional"))
    )
    (net (code "57") (name "P0.19") (class "Default")
      (node (ref "U1") (pin "P$AC15") (pinfunction "P0.19_P$AC15") (pintype "bidirectional"))
    )
    (net (code "58") (name "P0.20") (class "Default")
      (node (ref "U1") (pin "P$AD16") (pinfunction "P0.20_P$AD16") (pintype "bidirectional"))
    )
    (net (code "59") (name "P0.21") (class "Default")
      (node (ref "U1") (pin "P$AC17") (pinfunction "P0.21_P$AC17") (pintype "bidirectional"))
    )
    (net (code "60") (name "P0.22") (class "Default")
      (node (ref "U1") (pin "P$AD18") (pinfunction "P0.22_P$AD18") (pintype "bidirectional"))
    )
    (net (code "61") (name "P0.23") (class "Default")
      (node (ref "U1") (pin "P$AC19") (pinfunction "P0.23_P$AC19") (pintype "bidirectional"))
    )
    (net (code "62") (name "P0.24") (class "Default")
      (node (ref "U1") (pin "P$AD20") (pinfunction "P0.24_P$AD20") (pintype "bidirectional"))
    )
    (net (code "63") (name "P0.25") (class "Default")
      (node (ref "U1") (pin "P$AC21") (pinfunction "P0.25_P$AC21") (pintype "bidirectional"))
    )
    (net (code "64") (name "P0.26") (class "Default")
      (node (ref "U1") (pin "P$G1") (pinfunction "P0.26_P$G1") (pintype "bidirectional"))
    )
    (net (code "65") (name "P0.27") (class "Default")
      (node (ref "U1") (pin "P$H2") (pinfunction "P0.27_P$H2") (pintype "bidirectional"))
    )
    (net (code "66") (name "P0.28") (class "Default")
      (node (ref "U1") (pin "P$B11") (pinfunction "P0.28/AIN4_P$B11") (pintype "bidirectional"))
    )
    (net (code "67") (name "P0.29") (class "Default")
      (node (ref "U1") (pin "P$A10") (pinfunction "P0.29/AIN5_P$A10") (pintype "bidirectional"))
    )
    (net (code "68") (name "P0.30") (class "Default")
      (node (ref "U1") (pin "P$B9") (pinfunction "P0.30/AIN6_P$B9") (pintype "bidirectional"))
    )
    (net (code "69") (name "P0.31") (class "Default")
      (node (ref "U1") (pin "P$A8") (pinfunction "P0.31/AIN7_P$A8") (pintype "bidirectional"))
    )
    (net (code "70") (name "P1.01") (class "Default")
      (node (ref "Q1") (pin "1") (pinfunction "G_1") (pintype "bidirectional"))
      (node (ref "R_PWR_EPD") (pin "1") (pinfunction "1_1") (pintype "bidirectional"))
      (node (ref "U1") (pin "P$Y23") (pinfunction "P1.01_P$Y23") (pintype "bidirectional"))
    )
    (net (code "71") (name "P1.02") (class "Default")
      (node (ref "C29") (pin "2") (pinfunction "2_2") (pintype "passive"))
      (node (ref "R7") (pin "1") (pinfunction "1_1") (pintype "bidirectional"))
      (node (ref "SW_DN") (pin "2") (pinfunction "2_2") (pintype "passive"))
      (node (ref "U1") (pin "P$W24") (pinfunction "P1.02_P$W24") (pintype "bidirectional"))
    )
    (net (code "72") (name "P1.03") (class "Default")
      (node (ref "U1") (pin "P$V23") (pinfunction "P1.03_P$V23") (pintype "bidirectional"))
    )
    (net (code "73") (name "P1.04") (class "Default")
      (node (ref "U1") (pin "P$U24") (pinfunction "P1.04_P$U24") (pintype "bidirectional"))
    )
    (net (code "74") (name "P1.05") (class "Default")
      (node (ref "U1") (pin "P$T23") (pinfunction "P1.05_P$T23") (pintype "bidirectional"))
    )
    (net (code "75") (name "P1.06") (class "Default")
      (node (ref "U1") (pin "P$R24") (pinfunction "P1.06_P$R24") (pintype "bidirectional"))
    )
    (net (code "76") (name "P1.07") (class "Default")
      (node (ref "U1") (pin "P$P23") (pinfunction "P1.07_P$P23") (pintype "bidirectional"))
    )
    (net (code "77") (name "P1.09") (class "Default")
      (node (ref "U1") (pin "P$R1") (pinfunction "P1.09_P$R1") (pintype "bidirectional"))
    )
    (net (code "78") (name "P1.10") (class "Default")
      (node (ref "U1") (pin "P$A20") (pinfunction "P1.10_P$A20") (pintype "bidirectional"))
    )
    (net (code "79") (name "P1.11") (class "Default")
      (node (ref "U1") (pin "P$B19") (pinfunction "P1.11_P$B19") (pintype "bidirectional"))
    )
    (net (code "80") (name "P1.12") (class "Default")
      (node (ref "U1") (pin "P$B17") (pinfunction "P1.12_P$B17") (pintype "bidirectional"))
    )
    (net (code "81") (name "P1.13") (class "Default")
      (node (ref "U1") (pin "P$A16") (pinfunction "P1.13_P$A16") (pintype "bidirectional"))
    )
    (net (code "82") (name "P1.14") (class "Default")
      (node (ref "U1") (pin "P$B15") (pinfunction "P1.14_P$B15") (pintype "bidirectional"))
    )
    (net (code "83") (name "P1.15") (class "Default")
      (node (ref "U1") (pin "P$A14") (pinfunction "P1.15_P$A14") (pintype "bidirectional"))
    )
    (net (code "84") (name "PMIC_INT") (class "Default")
      (node (ref "IC1") (pin "A1") (pinfunction "~{INT}_A1") (pintype "bidirectional"))
      (node (ref "U1") (pin "P$T2") (pinfunction "P0.11_P$T2") (pintype "bidirectional"))
    )
    (net (code "85") (name "PREVGH") (class "Default")
      (node (ref "D5") (pin "1") (pinfunction "K_1") (pintype "bidirectional"))
      (node (ref "EPD_C9") (pin "2") (pinfunction "2_2") (pintype "passive"))
      (node (ref "J1") (pin "21") (pinfunction "21_21") (pintype "bidirectional"))
    )
    (net (code "86") (name "PREVGL") (class "Default")
      (node (ref "D2") (pin "2") (pinfunction "A_2") (pintype "bidirectional"))
      (node (ref "EPD_C11") (pin "2") (pinfunction "2_2") (pintype "passive"))
      (node (ref "J1") (pin "23") (pinfunction "23_23") (pintype "bidirectional"))
    )
    (net (code "87") (name "RESE") (class "Default")
      (node (ref "J1") (pin "3") (pinfunction "3_3") (pintype "bidirectional"))
      (node (ref "Q3") (pin "2") (pinfunction "S_2") (pintype "bidirectional"))
      (node (ref "R1_EP_DR") (pin "2") (pinfunction "2_2") (pintype "bidirectional"))
    )
    (net (code "88") (name "RESET") (class "Default")
      (node (ref "J2") (pin "6") (pinfunction "6_6") (pintype "bidirectional"))
      (node (ref "TP_RESET") (pin "TP") (pinfunction "TP_TP") (pintype "input"))
      (node (ref "U1") (pin "P$AC13") (pinfunction "P0.18/RESET_P$AC13") (pintype "bidirectional"))
    )
    (net (code "89") (name "SCK") (class "Default")
      (node (ref "J1") (pin "13") (pinfunction "13_13") (pintype "bidirectional"))
      (node (ref "U1") (pin "P$A12") (pinfunction "P0.02/AIN0_P$A12") (pintype "bidirectional"))
    )
    (net (code "90") (name "SCL") (class "Default")
      (node (ref "IC1") (pin "B1") (pinfunction "SCL_B1") (pintype "bidirectional"))
      (node (ref "IC2") (pin "C1") (pinfunction "SCL_C1") (pintype "bidirectional"))
      (node (ref "IC3") (pin "12") (pinfunction "SCX_12") (pintype "bidirectional"))
      (node (ref "R17") (pin "2") (pinfunction "2_2") (pintype "bidirectional"))
      (node (ref "R4") (pin "1") (pinfunction "1_1") (pintype "bidirectional"))
      (node (ref "TP_SCL") (pin "TP") (pinfunction "TP_TP") (pintype "input"))
      (node (ref "U1") (pin "P$M2") (pinfunction "P0.07_P$M2") (pintype "bidirectional"))
      (node (ref "U3") (pin "7") (pinfunction "SCL_7") (pintype "input"))
    )
    (net (code "91") (name "SDA") (class "Default")
      (node (ref "IC1") (pin "C1") (pinfunction "SDA_C1") (pintype "bidirectional"))
      (node (ref "IC2") (pin "B2") (pinfunction "SDA_B2") (pintype "bidirectional"))
      (node (ref "IC3") (pin "2") (pinfunction "SDX_2") (pintype "bidirectional"))
      (node (ref "R18") (pin "2") (pinfunction "2_2") (pintype "bidirectional"))
      (node (ref "R2") (pin "1") (pinfunction "1_1") (pintype "bidirectional"))
      (node (ref "TP_SDA") (pin "TP") (pinfunction "TP_TP") (pintype "input"))
      (node (ref "U1") (pin "P$L1") (pinfunction "P0.06_P$L1") (pintype "bidirectional"))
      (node (ref "U3") (pin "8") (pinfunction "SDA_8") (pintype "bidirectional"))
    )
    (net (code "92") (name "SWDCLK") (class "Default")
      (node (ref "J2") (pin "4") (pinfunction "4_4") (pintype "bidirectional"))
      (node (ref "TP_SWDCLK") (pin "TP") (pinfunction "TP_TP") (pintype "input"))
      (node (ref "U1") (pin "P$AA24") (pinfunction "SWDCLK_P$AA24") (pintype "input"))
    )
    (net (code "93") (name "SWDIO") (class "Default")
      (node (ref "J2") (pin "2") (pinfunction "2_2") (pintype "bidirectional"))
      (node (ref "TP_SWDIO") (pin "TP") (pinfunction "TP_TP") (pintype "input"))
      (node (ref "U1") (pin "P$AC24") (pinfunction "SWDIO_P$AC24") (pintype "bidirectional"))
    )
    (net (code "94") (name "SWO") (class "Default")
      (node (ref "TP_SWO") (pin "TP") (pinfunction "TP_TP") (pintype "input"))
      (node (ref "U1") (pin "P$AD22") (pinfunction "P1.00_P$AD22") (pintype "bidirectional"))
    )
    (net (code "95") (name "VBAT") (class "Default")
      (node (ref "C27") (pin "2") (pinfunction "2_2") (pintype "passive"))
      (node (ref "C37") (pin "2") (pinfunction "2_2") (pintype "passive"))
      (node (ref "IC1") (pin "C2") (pinfunction "BAT_C2") (pintype "bidirectional"))
      (node (ref "TP_VBAT") (pin "TP") (pinfunction "TP_TP") (pintype "input"))
      (node (ref "U3") (pin "2") (pinfunction "CELL_2") (pintype "power_in"))
      (node (ref "U3") (pin "3") (pinfunction "VDD_3") (pintype "power_in"))
    )
    (net (code "96") (name "VBUS") (class "Default")
      (node (ref "C21") (pin "1") (pinfunction "1_1") (pintype "passive"))
      (node (ref "C38") (pin "2") (pinfunction "2_2") (pintype "passive"))
      (node (ref "C42") (pin "1") (pinfunction "1_1") (pintype "passive"))
      (node (ref "C43") (pin "1") (pinfunction "1_1") (pintype "passive"))
      (node (ref "D3") (pin "5") (pinfunction "VBUS_5") (pintype "bidirectional"))
      (node (ref "IC1") (pin "A2") (pinfunction "IN_A2") (pintype "bidirectional"))
      (node (ref "J4") (pin "A4_B9") (pinfunction "VBUS_A4_B9") (pintype "power_in"))
      (node (ref "J4") (pin "A9_B4") (pinfunction "VBUS_A9_B4") (pintype "power_in"))
      (node (ref "U1") (pin "P$AD2") (pinfunction "VBUS_P$AD2") (pintype "power_in"))
    )
    (net (code "97") (name "VREG") (class "Default")
      (node (ref "C23") (pin "2") (pinfunction "2_2") (pintype "passive"))
      (node (ref "C24") (pin "2") (pinfunction "2_2") (pintype "passive"))
      (node (ref "C39") (pin "1") (pinfunction "1_1") (pintype "passive"))
      (node (ref "IC1") (pin "B2") (pinfunction "SYS_B2") (pintype "bidirectional"))
      (node (ref "IC9") (pin "A1") (pinfunction "EN_A1") (pintype "bidirectional"))
      (node (ref "IC9") (pin "A2") (pinfunction "VIN_1_A2") (pintype "bidirectional"))
      (node (ref "IC9") (pin "A3") (pinfunction "VIN_2_A3") (pintype "bidirectional"))
      (node (ref "TP_VREG") (pin "TP") (pinfunction "TP_TP") (pintype "input"))
    )
    (net (code "98") (name "unconnected-(ANT1-NC-Pad2)") (class "Default")
      (node (ref "ANT1") (pin "2") (pinfunction "NC_2") (pintype "no_connect"))
    )
    (net (code "99") (name "unconnected-(IC3-ASCL-Pad11)") (class "Default")
      (node (ref "IC3") (pin "11") (pinfunction "ASCL_11") (pintype "bidirectional"))
    )
    (net (code "100") (name "unconnected-(IC3-ASDA-Pad4)") (class "Default")
      (node (ref "IC3") (pin "4") (pinfunction "ASDA_4") (pintype "bidirectional"))
    )
    (net (code "101") (name "unconnected-(J1-Pad1)") (class "Default")
      (node (ref "J1") (pin "1") (pinfunction "1_1") (pintype "bidirectional"))
    )
    (net (code "102") (name "unconnected-(J1-Pad6)") (class "Default")
      (node (ref "J1") (pin "6") (pinfunction "6_6") (pintype "bidirectional"))
    )
    (net (code "103") (name "unconnected-(J1-Pad7)") (class "Default")
      (node (ref "J1") (pin "7") (pinfunction "7_7") (pintype "bidirectional"))
    )
    (net (code "104") (name "unconnected-(J4-SBU1-PadA8)") (class "Default")
      (node (ref "J4") (pin "A8") (pinfunction "SBU1_A8") (pintype "bidirectional"))
    )
    (net (code "105") (name "unconnected-(J4-SBU2-PadB8)") (class "Default")
      (node (ref "J4") (pin "B8") (pinfunction "SBU2_B8") (pintype "bidirectional"))
    )
    (net (code "106") (name "unconnected-(U1-DCCH-PadP$AB2)") (class "Default")
      (node (ref "U1") (pin "P$AB2") (pinfunction "DCCH_P$AB2") (pintype "bidirectional"))
    )
  )
)
